# RC_Receiver.net
KiCad netlist of a schematic drawn in EAGLE
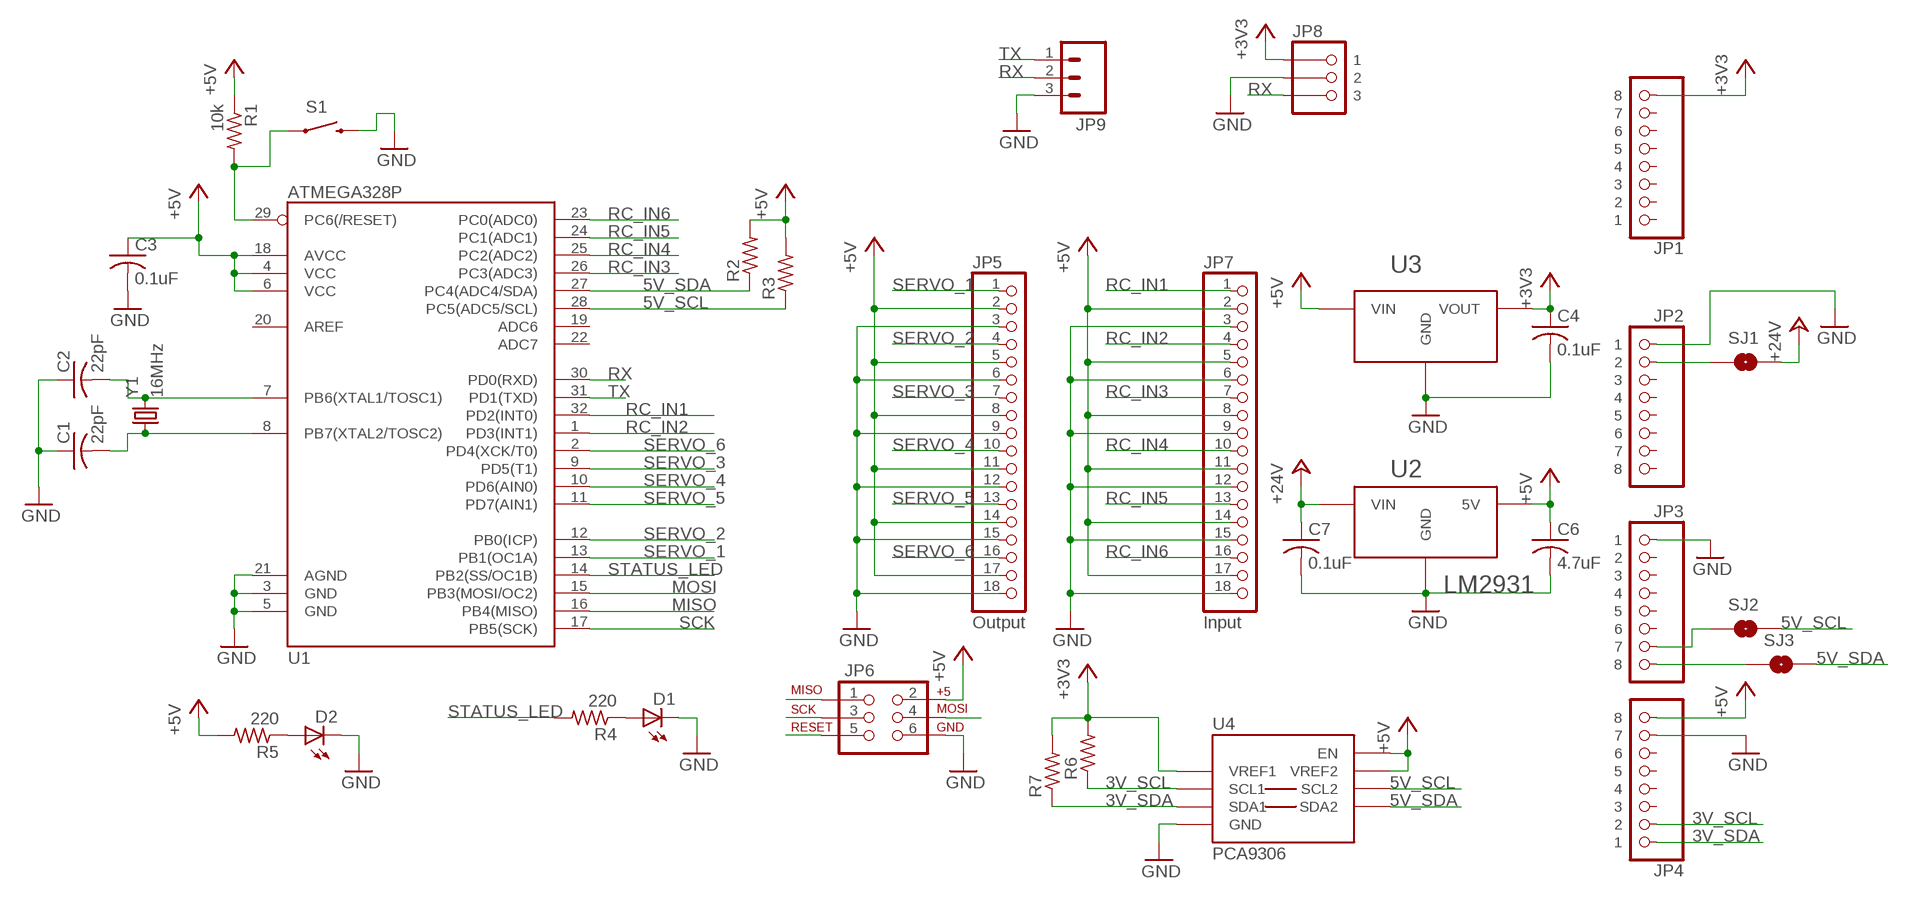
[diagram p0: schematic, sheet 1]

(export (version "E")
  (design (tool "Eeschema 10.0.6"))
  (components
    (comp (ref "C1")
      (value "22pF")
      (footprint "eagle-import:C0603")
      (libsource (lib "eagle-import") (part "C-USC0603"))
    )
    (comp (ref "C2")
      (value "22pF")
      (footprint "eagle-import:C0603")
      (libsource (lib "eagle-import") (part "C-USC0603"))
    )
    (comp (ref "C3")
      (value "0.1uF")
      (footprint "eagle-import:C0603")
      (libsource (lib "eagle-import") (part "C-USC0603"))
    )
    (comp (ref "C4")
      (value "0.1uF")
      (footprint "eagle-import:C0603")
      (libsource (lib "eagle-import") (part "C-USC0603"))
    )
    (comp (ref "C6")
      (value "4.7uF")
      (footprint "eagle-import:C0603")
      (libsource (lib "eagle-import") (part "C-USC0603"))
    )
    (comp (ref "C7")
      (value "0.1uF")
      (footprint "eagle-import:C0603")
      (libsource (lib "eagle-import") (part "C-USC0603"))
    )
    (comp (ref "D1")
      (value "LED-GREENLED-0805_NO_SILK")
      (footprint "eagle-import:LED-0805")
      (libsource (lib "eagle-import") (part "LED-GREENLED-0805_NO_SILK"))
    )
    (comp (ref "D2")
      (value "LED-GREENLED-0805_NO_SILK")
      (footprint "eagle-import:LED-0805")
      (libsource (lib "eagle-import") (part "LED-GREENLED-0805_NO_SILK"))
    )
    (comp (ref "JP1")
      (value "8-PIN_HEADER")
      (footprint "eagle-import:8-PIN_RECEPTACLE_LOCK_NO-SS")
      (libsource (lib "eagle-import") (part "8-PIN_HEADER"))
    )
    (comp (ref "JP2")
      (value "8-PIN_HEADER")
      (footprint "eagle-import:8-PIN_RECEPTACLE_LOCK_NO-SS")
      (libsource (lib "eagle-import") (part "8-PIN_HEADER"))
    )
    (comp (ref "JP3")
      (value "8-PIN_HEADER")
      (footprint "eagle-import:8-PIN_RECEPTACLE_LOCK_NO-SS")
      (libsource (lib "eagle-import") (part "8-PIN_HEADER"))
    )
    (comp (ref "JP4")
      (value "8-PIN_HEADER")
      (footprint "eagle-import:8-PIN_RECEPTACLE_LOCK_NO-SS")
      (libsource (lib "eagle-import") (part "8-PIN_HEADER"))
    )
    (comp (ref "JP5")
      (value "Output")
      (footprint "eagle-import:3X6_PTH_HEADER")
      (libsource (lib "eagle-import") (part "18_PIN_HEADER3X6_PTH_HEADER"))
    )
    (comp (ref "JP6")
      (value "AVR_SPI_PRG_62X3_LOCK")
      (footprint "eagle-import:2X3_LOCK")
      (libsource (lib "eagle-import") (part "AVR_SPI_PRG_62X3_LOCK"))
    )
    (comp (ref "JP7")
      (value "Input")
      (footprint "eagle-import:3X6_PTH_HEADER")
      (libsource (lib "eagle-import") (part "18_PIN_HEADER3X6_PTH_HEADER"))
    )
    (comp (ref "JP8")
      (value "3-PIN_JST_ZH_PTH_CONNECTORRIGHT_ANGLE_PTH")
      (footprint "eagle-import:3-PIN_JST_ZH_CONNECTOR_TH")
      (fields (field (name "PART#") "455-1670-ND"))
      (libsource (lib "eagle-import") (part "3-PIN_JST_ZH_PTH_CONNECTORRIGHT_ANGLE_PTH"))
    )
    (comp (ref "JP9")
      (value "M03LOCK")
      (footprint "eagle-import:1X03_LOCK")
      (libsource (lib "eagle-import") (part "M03LOCK"))
    )
    (comp (ref "R1")
      (value "10k")
      (footprint "eagle-import:R0603")
      (libsource (lib "eagle-import") (part "R-US_R0603"))
    )
    (comp (ref "R2")
      (value "R-US_R0603")
      (footprint "eagle-import:R0603")
      (libsource (lib "eagle-import") (part "R-US_R0603"))
    )
    (comp (ref "R3")
      (value "R-US_R0603")
      (footprint "eagle-import:R0603")
      (libsource (lib "eagle-import") (part "R-US_R0603"))
    )
    (comp (ref "R4")
      (value "220")
      (footprint "eagle-import:R0603")
      (libsource (lib "eagle-import") (part "R-US_R0603"))
    )
    (comp (ref "R5")
      (value "220")
      (footprint "eagle-import:R0603")
      (libsource (lib "eagle-import") (part "R-US_R0603"))
    )
    (comp (ref "R6")
      (value "R-US_R0603")
      (footprint "eagle-import:R0603")
      (libsource (lib "eagle-import") (part "R-US_R0603"))
    )
    (comp (ref "R7")
      (value "R-US_R0603")
      (footprint "eagle-import:R0603")
      (libsource (lib "eagle-import") (part "R-US_R0603"))
    )
    (comp (ref "S1")
      (value "SWITCH-MOMENTARY-2SMD")
      (footprint "eagle-import:TACTILE_SWITCH_SMD")
      (libsource (lib "eagle-import") (part "SWITCH-MOMENTARY-2SMD"))
    )
    (comp (ref "SJ1")
      (value "SOLDERJUMPERTRACE")
      (footprint "eagle-import:SJ_2S-TRACE")
      (libsource (lib "eagle-import") (part "SOLDERJUMPERTRACE"))
    )
    (comp (ref "SJ2")
      (value "SOLDERJUMPERNC2")
      (footprint "eagle-import:SJ_2S-NOTRACE")
      (libsource (lib "eagle-import") (part "SOLDERJUMPERNC2"))
    )
    (comp (ref "SJ3")
      (value "SOLDERJUMPERNC2")
      (footprint "eagle-import:SJ_2S-NOTRACE")
      (libsource (lib "eagle-import") (part "SOLDERJUMPERNC2"))
    )
    (comp (ref "U1")
      (value "ATMEGA328P")
      (footprint "eagle-import:TQFP32-08")
      (libsource (lib "eagle-import") (part "ATMEGA328_SMT"))
    )
    (comp (ref "U2")
      (value "LM2931")
      (footprint "eagle-import:TO263")
      (fields (field (name "PART#") "lm2931"))
      (libsource (lib "eagle-import") (part "LM2931"))
    )
    (comp (ref "U3")
      (value "AP7313SOT23R")
      (footprint "eagle-import:SOT23")
      (fields (field (name "PART#") "AP7313-33SRG-7"))
      (libsource (lib "eagle-import") (part "AP7313SOT23R"))
    )
    (comp (ref "U4")
      (value "PCA9306")
      (footprint "eagle-import:SOIC-8")
      (libsource (lib "eagle-import") (part "PCA9306"))
    )
    (comp (ref "Y1")
      (value "16MHz")
      (footprint "eagle-import:CRYSTAL-SMD-5X3")
      (fields (field (name "PART#") "887-1104-1-ND"))
      (libsource (lib "eagle-import") (part "CRYSTAL5X3"))
    )
  )
  (nets
    (net (code "1") (name "+3V3") (class "Default")
      (node (ref "C4") (pin "1") (pinfunction "1_1") (pintype "passive"))
      (node (ref "JP1") (pin "P$8") (pinfunction "8_P$8") (pintype "passive"))
      (node (ref "JP8") (pin "P$1") (pinfunction "1_P$1") (pintype "passive"))
      (node (ref "R6") (pin "2") (pinfunction "2_2") (pintype "passive"))
      (node (ref "R7") (pin "2") (pinfunction "2_2") (pintype "passive"))
      (node (ref "U3") (pin "P$2") (pinfunction "VOUT_P$2") (pintype "bidirectional"))
      (node (ref "U4") (pin "P$2") (pinfunction "VREF1_P$2") (pintype "bidirectional"))
    )
    (net (code "2") (name "+5V") (class "Default")
      (node (ref "C3") (pin "1") (pinfunction "1_1") (pintype "passive"))
      (node (ref "C6") (pin "1") (pinfunction "1_1") (pintype "passive"))
      (node (ref "JP4") (pin "P$8") (pinfunction "8_P$8") (pintype "passive"))
      (node (ref "JP5") (pin "11") (pinfunction "11_11") (pintype "passive"))
      (node (ref "JP5") (pin "14") (pinfunction "14_14") (pintype "passive"))
      (node (ref "JP5") (pin "17") (pinfunction "17_17") (pintype "passive"))
      (node (ref "JP5") (pin "2") (pinfunction "2_2") (pintype "passive"))
      (node (ref "JP5") (pin "5") (pinfunction "5_5") (pintype "passive"))
      (node (ref "JP5") (pin "8") (pinfunction "8_8") (pintype "passive"))
      (node (ref "JP6") (pin "2") (pinfunction "2_2") (pintype "passive"))
      (node (ref "JP7") (pin "11") (pinfunction "11_11") (pintype "passive"))
      (node (ref "JP7") (pin "14") (pinfunction "14_14") (pintype "passive"))
      (node (ref "JP7") (pin "17") (pinfunction "17_17") (pintype "passive"))
      (node (ref "JP7") (pin "2") (pinfunction "2_2") (pintype "passive"))
      (node (ref "JP7") (pin "5") (pinfunction "5_5") (pintype "passive"))
      (node (ref "JP7") (pin "8") (pinfunction "8_8") (pintype "passive"))
      (node (ref "R1") (pin "1") (pinfunction "1_1") (pintype "passive"))
      (node (ref "R2") (pin "2") (pinfunction "2_2") (pintype "passive"))
      (node (ref "R3") (pin "2") (pinfunction "2_2") (pintype "passive"))
      (node (ref "R5") (pin "2") (pinfunction "2_2") (pintype "passive"))
      (node (ref "U1") (pin "18") (pinfunction "AVCC_18") (pintype "bidirectional"))
      (node (ref "U1") (pin "4") (pinfunction "VCC_4") (pintype "bidirectional"))
      (node (ref "U1") (pin "6") (pinfunction "VCC_6") (pintype "bidirectional"))
      (node (ref "U2") (pin "P$3") (pinfunction "5V_P$3") (pintype "bidirectional"))
      (node (ref "U3") (pin "P$3") (pinfunction "VIN_P$3") (pintype "bidirectional"))
      (node (ref "U4") (pin "P$7") (pinfunction "VREF2_P$7") (pintype "bidirectional"))
      (node (ref "U4") (pin "P$8") (pinfunction "EN_P$8") (pintype "bidirectional"))
    )
    (net (code "3") (name "+24V") (class "Default")
      (node (ref "C7") (pin "1") (pinfunction "1_1") (pintype "passive"))
      (node (ref "SJ1") (pin "2") (pinfunction "2_2") (pintype "passive"))
      (node (ref "U2") (pin "P$2") (pinfunction "VIN_P$2") (pintype "bidirectional"))
    )
    (net (code "4") (name "/3V_SCL") (class "Default")
      (node (ref "JP4") (pin "P$2") (pinfunction "2_P$2") (pintype "passive"))
      (node (ref "R6") (pin "1") (pinfunction "1_1") (pintype "passive"))
      (node (ref "U4") (pin "P$3") (pinfunction "SCL1_P$3") (pintype "bidirectional"))
    )
    (net (code "5") (name "/3V_SDA") (class "Default")
      (node (ref "JP4") (pin "P$1") (pinfunction "1_P$1") (pintype "passive"))
      (node (ref "R7") (pin "1") (pinfunction "1_1") (pintype "passive"))
      (node (ref "U4") (pin "P$4") (pinfunction "SDA1_P$4") (pintype "bidirectional"))
    )
    (net (code "6") (name "/5V_SCL") (class "Default")
      (node (ref "R3") (pin "1") (pinfunction "1_1") (pintype "passive"))
      (node (ref "SJ2") (pin "2") (pinfunction "2_2") (pintype "passive"))
      (node (ref "U1") (pin "28") (pinfunction "PC5(ADC5/SCL)_28") (pintype "bidirectional"))
      (node (ref "U4") (pin "P$6") (pinfunction "SCL2_P$6") (pintype "bidirectional"))
    )
    (net (code "7") (name "/5V_SDA") (class "Default")
      (node (ref "R2") (pin "1") (pinfunction "1_1") (pintype "passive"))
      (node (ref "SJ3") (pin "2") (pinfunction "2_2") (pintype "passive"))
      (node (ref "U1") (pin "27") (pinfunction "PC4(ADC4/SDA)_27") (pintype "bidirectional"))
      (node (ref "U4") (pin "P$5") (pinfunction "SDA2_P$5") (pintype "bidirectional"))
    )
    (net (code "8") (name "/MISO") (class "Default")
      (node (ref "JP6") (pin "1") (pinfunction "1_1") (pintype "passive"))
      (node (ref "U1") (pin "16") (pinfunction "PB4(MISO)_16") (pintype "bidirectional"))
    )
    (net (code "9") (name "/MOSI") (class "Default")
      (node (ref "JP6") (pin "4") (pinfunction "4_4") (pintype "passive"))
      (node (ref "U1") (pin "15") (pinfunction "PB3(MOSI/OC2)_15") (pintype "bidirectional"))
    )
    (net (code "10") (name "/RC_IN1") (class "Default")
      (node (ref "JP7") (pin "1") (pinfunction "1_1") (pintype "passive"))
      (node (ref "U1") (pin "32") (pinfunction "PD2(INT0)_32") (pintype "bidirectional"))
    )
    (net (code "11") (name "/RC_IN2") (class "Default")
      (node (ref "JP7") (pin "4") (pinfunction "4_4") (pintype "passive"))
      (node (ref "U1") (pin "1") (pinfunction "PD3(INT1)_1") (pintype "bidirectional"))
    )
    (net (code "12") (name "/RC_IN3") (class "Default")
      (node (ref "JP7") (pin "7") (pinfunction "7_7") (pintype "passive"))
      (node (ref "U1") (pin "26") (pinfunction "PC3(ADC3)_26") (pintype "bidirectional"))
    )
    (net (code "13") (name "/RC_IN4") (class "Default")
      (node (ref "JP7") (pin "10") (pinfunction "10_10") (pintype "passive"))
      (node (ref "U1") (pin "25") (pinfunction "PC2(ADC2)_25") (pintype "bidirectional"))
    )
    (net (code "14") (name "/RC_IN5") (class "Default")
      (node (ref "JP7") (pin "13") (pinfunction "13_13") (pintype "passive"))
      (node (ref "U1") (pin "24") (pinfunction "PC1(ADC1)_24") (pintype "bidirectional"))
    )
    (net (code "15") (name "/RC_IN6") (class "Default")
      (node (ref "JP7") (pin "16") (pinfunction "16_16") (pintype "passive"))
      (node (ref "U1") (pin "23") (pinfunction "PC0(ADC0)_23") (pintype "bidirectional"))
    )
    (net (code "16") (name "/RESET") (class "Default")
      (node (ref "JP6") (pin "5") (pinfunction "5_5") (pintype "passive"))
      (node (ref "R1") (pin "2") (pinfunction "2_2") (pintype "passive"))
      (node (ref "S1") (pin "1") (pinfunction "1_1") (pintype "passive"))
      (node (ref "U1") (pin "29") (pinfunction "PC6(/RESET)_29") (pintype "bidirectional"))
    )
    (net (code "17") (name "/RX") (class "Default")
      (node (ref "JP8") (pin "P$3") (pinfunction "3_P$3") (pintype "passive"))
      (node (ref "JP9") (pin "2") (pinfunction "2_2") (pintype "passive"))
      (node (ref "U1") (pin "30") (pinfunction "PD0(RXD)_30") (pintype "bidirectional"))
    )
    (net (code "18") (name "/SCK") (class "Default")
      (node (ref "JP6") (pin "3") (pinfunction "3_3") (pintype "passive"))
      (node (ref "U1") (pin "17") (pinfunction "PB5(SCK)_17") (pintype "bidirectional"))
    )
    (net (code "19") (name "/SERVO_1") (class "Default")
      (node (ref "JP5") (pin "1") (pinfunction "1_1") (pintype "passive"))
      (node (ref "U1") (pin "13") (pinfunction "PB1(OC1A)_13") (pintype "bidirectional"))
    )
    (net (code "20") (name "/SERVO_2") (class "Default")
      (node (ref "JP5") (pin "4") (pinfunction "4_4") (pintype "passive"))
      (node (ref "U1") (pin "12") (pinfunction "PB0(ICP)_12") (pintype "bidirectional"))
    )
    (net (code "21") (name "/SERVO_3") (class "Default")
      (node (ref "JP5") (pin "7") (pinfunction "7_7") (pintype "passive"))
      (node (ref "U1") (pin "9") (pinfunction "PD5(T1)_9") (pintype "bidirectional"))
    )
    (net (code "22") (name "/SERVO_4") (class "Default")
      (node (ref "JP5") (pin "10") (pinfunction "10_10") (pintype "passive"))
      (node (ref "U1") (pin "10") (pinfunction "PD6(AIN0)_10") (pintype "bidirectional"))
    )
    (net (code "23") (name "/SERVO_5") (class "Default")
      (node (ref "JP5") (pin "13") (pinfunction "13_13") (pintype "passive"))
      (node (ref "U1") (pin "11") (pinfunction "PD7(AIN1)_11") (pintype "bidirectional"))
    )
    (net (code "24") (name "/SERVO_6") (class "Default")
      (node (ref "JP5") (pin "16") (pinfunction "16_16") (pintype "passive"))
      (node (ref "U1") (pin "2") (pinfunction "PD4(XCK/T0)_2") (pintype "bidirectional"))
    )
    (net (code "25") (name "/STATUS_LED") (class "Default")
      (node (ref "R4") (pin "2") (pinfunction "2_2") (pintype "passive"))
      (node (ref "U1") (pin "14") (pinfunction "PB2(SS/OC1B)_14") (pintype "bidirectional"))
    )
    (net (code "26") (name "/TX") (class "Default")
      (node (ref "JP9") (pin "1") (pinfunction "1_1") (pintype "passive"))
      (node (ref "U1") (pin "31") (pinfunction "PD1(TXD)_31") (pintype "bidirectional"))
    )
    (net (code "27") (name "GND") (class "Default")
      (node (ref "C1") (pin "1") (pinfunction "1_1") (pintype "passive"))
      (node (ref "C2") (pin "1") (pinfunction "1_1") (pintype "passive"))
      (node (ref "C3") (pin "2") (pinfunction "2_2") (pintype "passive"))
      (node (ref "C4") (pin "2") (pinfunction "2_2") (pintype "passive"))
      (node (ref "C6") (pin "2") (pinfunction "2_2") (pintype "passive"))
      (node (ref "C7") (pin "2") (pinfunction "2_2") (pintype "passive"))
      (node (ref "D1") (pin "2") (pinfunction "C_2") (pintype "passive"))
      (node (ref "D2") (pin "2") (pinfunction "C_2") (pintype "passive"))
      (node (ref "JP2") (pin "P$1") (pinfunction "1_P$1") (pintype "passive"))
      (node (ref "JP3") (pin "P$1") (pinfunction "1_P$1") (pintype "passive"))
      (node (ref "JP4") (pin "P$7") (pinfunction "7_P$7") (pintype "passive"))
      (node (ref "JP5") (pin "12") (pinfunction "12_12") (pintype "passive"))
      (node (ref "JP5") (pin "15") (pinfunction "15_15") (pintype "passive"))
      (node (ref "JP5") (pin "18") (pinfunction "18_18") (pintype "passive"))
      (node (ref "JP5") (pin "3") (pinfunction "3_3") (pintype "passive"))
      (node (ref "JP5") (pin "6") (pinfunction "6_6") (pintype "passive"))
      (node (ref "JP5") (pin "9") (pinfunction "9_9") (pintype "passive"))
      (node (ref "JP6") (pin "6") (pinfunction "6_6") (pintype "passive"))
      (node (ref "JP7") (pin "12") (pinfunction "12_12") (pintype "passive"))
      (node (ref "JP7") (pin "15") (pinfunction "15_15") (pintype "passive"))
      (node (ref "JP7") (pin "18") (pinfunction "18_18") (pintype "passive"))
      (node (ref "JP7") (pin "3") (pinfunction "3_3") (pintype "passive"))
      (node (ref "JP7") (pin "6") (pinfunction "6_6") (pintype "passive"))
      (node (ref "JP7") (pin "9") (pinfunction "9_9") (pintype "passive"))
      (node (ref "JP8") (pin "P$2") (pinfunction "2_P$2") (pintype "passive"))
      (node (ref "JP9") (pin "3") (pinfunction "3_3") (pintype "passive"))
      (node (ref "S1") (pin "3") (pinfunction "2_3") (pintype "passive"))
      (node (ref "U1") (pin "21") (pinfunction "AGND_21") (pintype "bidirectional"))
      (node (ref "U1") (pin "3") (pinfunction "GND_3") (pintype "bidirectional"))
      (node (ref "U1") (pin "5") (pinfunction "GND_5") (pintype "bidirectional"))
      (node (ref "U2") (pin "P$1") (pinfunction "GND_P$1") (pintype "bidirectional"))
      (node (ref "U3") (pin "P$1") (pinfunction "GND_P$1") (pintype "bidirectional"))
      (node (ref "U4") (pin "P$1") (pinfunction "GND_P$1") (pintype "bidirectional"))
    )
    (net (code "28") (name "Net-(D1-A)") (class "Default")
      (node (ref "D1") (pin "1") (pinfunction "A_1") (pintype "passive"))
      (node (ref "R4") (pin "1") (pinfunction "1_1") (pintype "passive"))
    )
    (net (code "29") (name "Net-(D2-A)") (class "Default")
      (node (ref "D2") (pin "1") (pinfunction "A_1") (pintype "passive"))
      (node (ref "R5") (pin "1") (pinfunction "1_1") (pintype "passive"))
    )
    (net (code "30") (name "Net-(JP2-2)") (class "Default")
      (node (ref "JP2") (pin "P$2") (pinfunction "2_P$2") (pintype "passive"))
      (node (ref "SJ1") (pin "1") (pinfunction "1_1") (pintype "passive"))
    )
    (net (code "31") (name "Net-(JP3-7)") (class "Default")
      (node (ref "JP3") (pin "P$7") (pinfunction "7_P$7") (pintype "passive"))
      (node (ref "SJ2") (pin "1") (pinfunction "1_1") (pintype "passive"))
    )
    (net (code "32") (name "Net-(JP3-8)") (class "Default")
      (node (ref "JP3") (pin "P$8") (pinfunction "8_P$8") (pintype "passive"))
      (node (ref "SJ3") (pin "1") (pinfunction "1_1") (pintype "passive"))
    )
    (net (code "33") (name "Net-(U1-PB6(XTAL1{slash}TOSC1))") (class "Default")
      (node (ref "C2") (pin "2") (pinfunction "2_2") (pintype "passive"))
      (node (ref "U1") (pin "7") (pinfunction "PB6(XTAL1/TOSC1)_7") (pintype "bidirectional"))
      (node (ref "Y1") (pin "3") (pinfunction "2_3") (pintype "passive"))
    )
    (net (code "34") (name "Net-(U1-PB7(XTAL2{slash}TOSC2))") (class "Default")
      (node (ref "C1") (pin "2") (pinfunction "2_2") (pintype "passive"))
      (node (ref "U1") (pin "8") (pinfunction "PB7(XTAL2/TOSC2)_8") (pintype "bidirectional"))
      (node (ref "Y1") (pin "1") (pinfunction "1_1") (pintype "passive"))
    )
    (net (code "35") (name "unconnected-(JP1-1-PadP$1)") (class "Default")
      (node (ref "JP1") (pin "P$1") (pinfunction "1_P$1") (pintype "passive"))
    )
    (net (code "36") (name "unconnected-(JP1-2-PadP$2)") (class "Default")
      (node (ref "JP1") (pin "P$2") (pinfunction "2_P$2") (pintype "passive"))
    )
    (net (code "37") (name "unconnected-(JP1-3-PadP$3)") (class "Default")
      (node (ref "JP1") (pin "P$3") (pinfunction "3_P$3") (pintype "passive"))
    )
    (net (code "38") (name "unconnected-(JP1-4-PadP$4)") (class "Default")
      (node (ref "JP1") (pin "P$4") (pinfunction "4_P$4") (pintype "passive"))
    )
    (net (code "39") (name "unconnected-(JP1-5-PadP$5)") (class "Default")
      (node (ref "JP1") (pin "P$5") (pinfunction "5_P$5") (pintype "passive"))
    )
    (net (code "40") (name "unconnected-(JP1-6-PadP$6)") (class "Default")
      (node (ref "JP1") (pin "P$6") (pinfunction "6_P$6") (pintype "passive"))
    )
    (net (code "41") (name "unconnected-(JP1-7-PadP$7)") (class "Default")
      (node (ref "JP1") (pin "P$7") (pinfunction "7_P$7") (pintype "passive"))
    )
    (net (code "42") (name "unconnected-(JP2-3-PadP$3)") (class "Default")
      (node (ref "JP2") (pin "P$3") (pinfunction "3_P$3") (pintype "passive"))
    )
    (net (code "43") (name "unconnected-(JP2-4-PadP$4)") (class "Default")
      (node (ref "JP2") (pin "P$4") (pinfunction "4_P$4") (pintype "passive"))
    )
    (net (code "44") (name "unconnected-(JP2-5-PadP$5)") (class "Default")
      (node (ref "JP2") (pin "P$5") (pinfunction "5_P$5") (pintype "passive"))
    )
    (net (code "45") (name "unconnected-(JP2-6-PadP$6)") (class "Default")
      (node (ref "JP2") (pin "P$6") (pinfunction "6_P$6") (pintype "passive"))
    )
    (net (code "46") (name "unconnected-(JP2-7-PadP$7)") (class "Default")
      (node (ref "JP2") (pin "P$7") (pinfunction "7_P$7") (pintype "passive"))
    )
    (net (code "47") (name "unconnected-(JP2-8-PadP$8)") (class "Default")
      (node (ref "JP2") (pin "P$8") (pinfunction "8_P$8") (pintype "passive"))
    )
    (net (code "48") (name "unconnected-(JP3-2-PadP$2)") (class "Default")
      (node (ref "JP3") (pin "P$2") (pinfunction "2_P$2") (pintype "passive"))
    )
    (net (code "49") (name "unconnected-(JP3-3-PadP$3)") (class "Default")
      (node (ref "JP3") (pin "P$3") (pinfunction "3_P$3") (pintype "passive"))
    )
    (net (code "50") (name "unconnected-(JP3-4-PadP$4)") (class "Default")
      (node (ref "JP3") (pin "P$4") (pinfunction "4_P$4") (pintype "passive"))
    )
    (net (code "51") (name "unconnected-(JP3-5-PadP$5)") (class "Default")
      (node (ref "JP3") (pin "P$5") (pinfunction "5_P$5") (pintype "passive"))
    )
    (net (code "52") (name "unconnected-(JP3-6-PadP$6)") (class "Default")
      (node (ref "JP3") (pin "P$6") (pinfunction "6_P$6") (pintype "passive"))
    )
    (net (code "53") (name "unconnected-(JP4-3-PadP$3)") (class "Default")
      (node (ref "JP4") (pin "P$3") (pinfunction "3_P$3") (pintype "passive"))
    )
    (net (code "54") (name "unconnected-(JP4-4-PadP$4)") (class "Default")
      (node (ref "JP4") (pin "P$4") (pinfunction "4_P$4") (pintype "passive"))
    )
    (net (code "55") (name "unconnected-(JP4-5-PadP$5)") (class "Default")
      (node (ref "JP4") (pin "P$5") (pinfunction "5_P$5") (pintype "passive"))
    )
    (net (code "56") (name "unconnected-(JP4-6-PadP$6)") (class "Default")
      (node (ref "JP4") (pin "P$6") (pinfunction "6_P$6") (pintype "passive"))
    )
    (net (code "57") (name "unconnected-(U1-ADC6-Pad19)") (class "Default")
      (node (ref "U1") (pin "19") (pinfunction "ADC6_19") (pintype "bidirectional"))
    )
    (net (code "58") (name "unconnected-(U1-ADC7-Pad22)") (class "Default")
      (node (ref "U1") (pin "22") (pinfunction "ADC7_22") (pintype "bidirectional"))
    )
    (net (code "59") (name "unconnected-(U1-AREF-Pad20)") (class "Default")
      (node (ref "U1") (pin "20") (pinfunction "AREF_20") (pintype "bidirectional"))
    )
  )
)
